# micro.net
KiCad netlist of a schematic drawn in Altium Designer
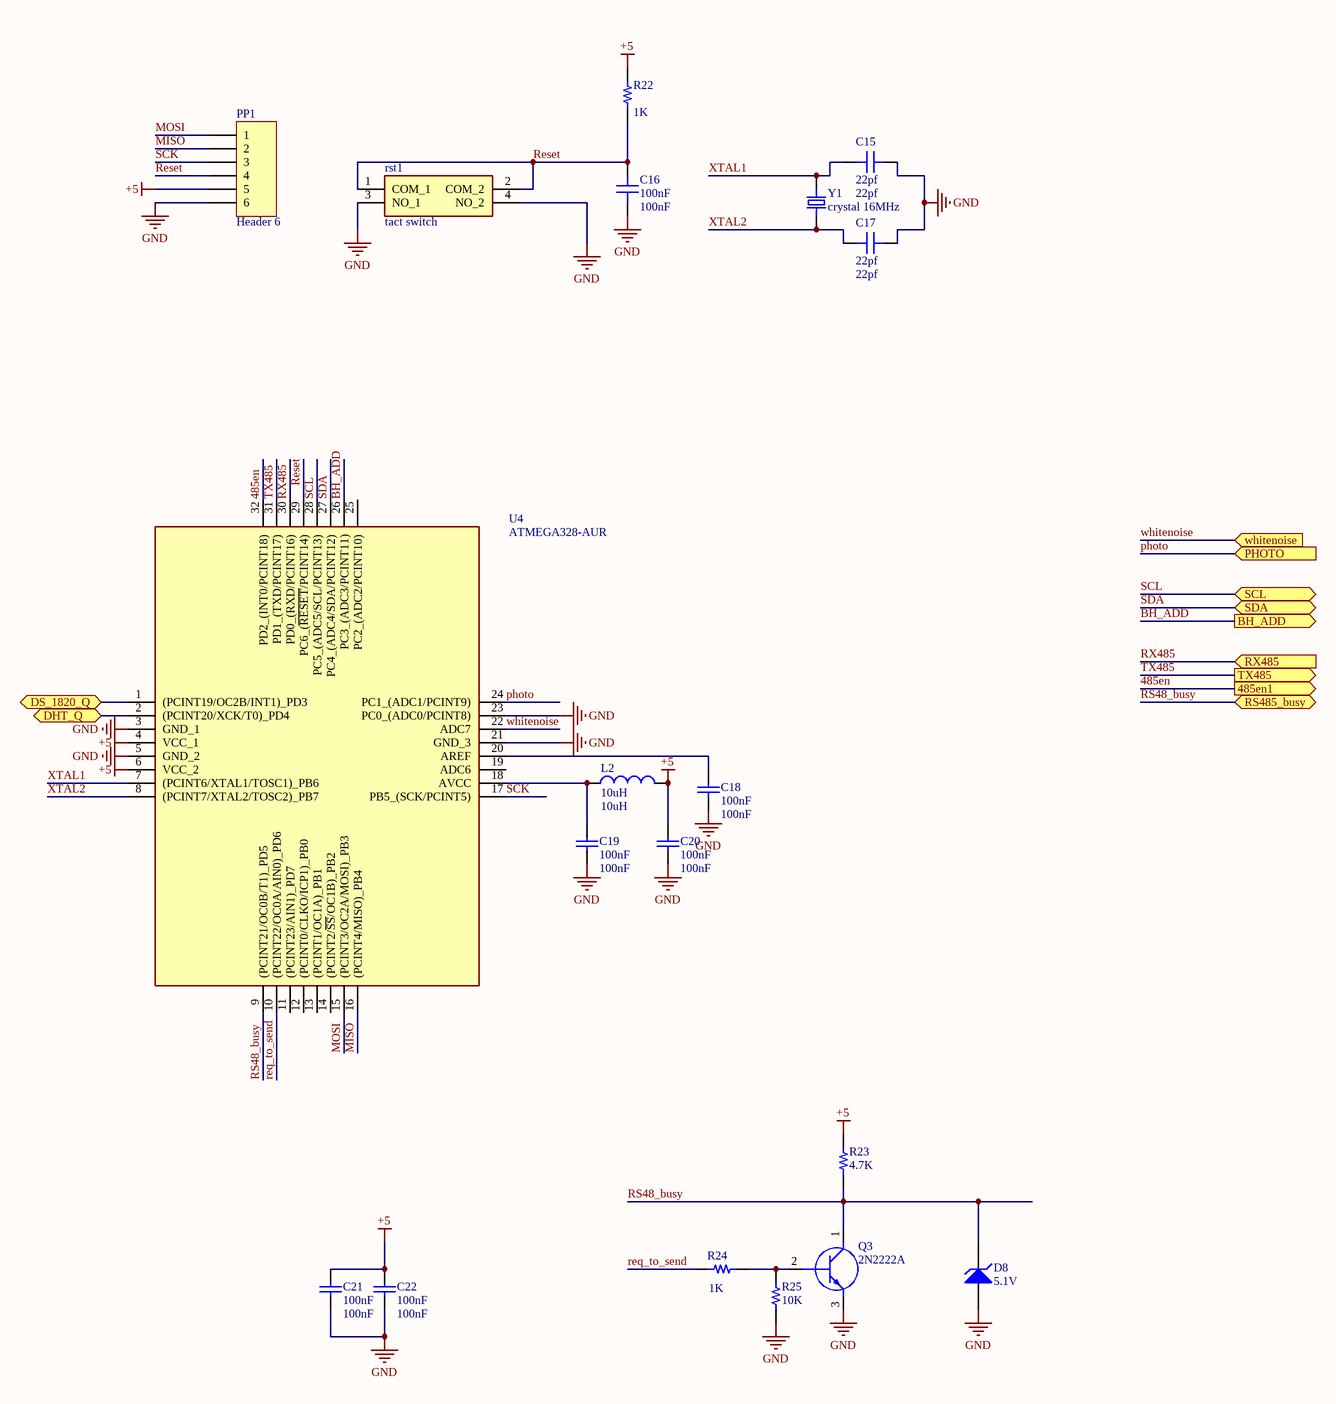
[diagram p0: micro.SchDoc]

(export (version "E")
  (design (tool "Eeschema 10.0.6"))
  (components
    (comp (ref "C15")
      (value "22pf")
      (footprint "0603C")
      (description "CAP SMD 0603")
      (fields (field (name "PART NUMBER") "C0805X106K9RAC7800") (field (name "ALTIUM_VALUE") "22pf"))
      (libsource (lib "lamp control-ver2") (part "Capacitor"))
    )
    (comp (ref "C16")
      (value "100nF")
      (footprint "0603C")
      (description "CAP SMD 0603")
      (fields (field (name "PART NUMBER") "C0805X106K9RAC7800") (field (name "ALTIUM_VALUE") "100nF"))
      (libsource (lib "lamp control-ver2") (part "Capacitor"))
    )
    (comp (ref "C17")
      (value "22pf")
      (footprint "0603C")
      (description "CAP SMD 0603")
      (fields (field (name "PART NUMBER") "C0805X106K9RAC7800") (field (name "ALTIUM_VALUE") "22pf"))
      (libsource (lib "lamp control-ver2") (part "Capacitor"))
    )
    (comp (ref "C18")
      (value "100nF")
      (footprint "0603C")
      (description "CAP SMD 0603")
      (fields (field (name "ALTIUM_VALUE") "100nF") (field (name "PUBLISHER") "Altium Limited"))
      (libsource (lib "Miscellaneous Devices") (part "Cap"))
    )
    (comp (ref "C19")
      (value "100nF")
      (footprint "0603C")
      (description "CAP SMD 0603")
      (fields (field (name "ALTIUM_VALUE") "100nF") (field (name "PUBLISHER") "Altium Limited"))
      (libsource (lib "Miscellaneous Devices") (part "Cap"))
    )
    (comp (ref "C20")
      (value "100nF")
      (footprint "0603C")
      (description "CAP SMD 0603")
      (fields (field (name "ALTIUM_VALUE") "100nF") (field (name "PUBLISHER") "Altium Limited"))
      (libsource (lib "Miscellaneous Devices") (part "Cap"))
    )
    (comp (ref "C21")
      (value "100nF")
      (footprint "0603C")
      (description "CAP SMD 0603")
      (fields (field (name "ALTIUM_VALUE") "100nF") (field (name "PUBLISHER") "Altium Limited"))
      (libsource (lib "Miscellaneous Devices") (part "Cap"))
    )
    (comp (ref "C22")
      (value "100nF")
      (footprint "0603C")
      (description "CAP SMD 0603")
      (fields (field (name "ALTIUM_VALUE") "100nF") (field (name "PUBLISHER") "Altium Limited"))
      (libsource (lib "Miscellaneous Devices") (part "Cap"))
    )
    (comp (ref "D8")
      (value "5.1V")
      (footprint "Diode 1n4148 SMD")
      (description "Zener Diode 5.1v")
      (fields (field (name "PUBLISHER") "Altium Limited"))
      (libsource (lib "Miscellaneous Devices") (part "D Zener"))
    )
    (comp (ref "L2")
      (value "10uH")
      (footprint "IND1206")
      (description "Inductor 1206")
      (fields (field (name "ALTIUM_VALUE") "10uH") (field (name "PUBLISHER") "Altium Limited"))
      (libsource (lib "Miscellaneous Devices") (part "Inductor"))
    )
    (comp (ref "PP1")
      (value "Header 6")
      (footprint "HDR1X6")
      (description "Header, 6-Pin , female")
      (fields (field (name "PUBLISHER") "Altium Limited"))
      (libsource (lib "Miscellaneous Connectors") (part "Header 6"))
    )
    (comp (ref "Q3")
      (value "2N2222A")
      (footprint "soT95p280x130-3n")
      (description "Transistor BJT NPN SMD")
      (libsource (lib "*") (part "2N2222A"))
    )
    (comp (ref "R22")
      (value "1K")
      (footprint "0603R")
      (description "RES SMD 0603")
      (fields (field (name "PART NUMBER") "RCS0805100KFKEA"))
      (libsource (lib "lamp control-ver2") (part "Resistor"))
    )
    (comp (ref "R23")
      (value "4.7K")
      (footprint "0603R")
      (description "RES SMD 0603")
      (fields (field (name "PART NUMBER") "RCS0805100KFKEA"))
      (libsource (lib "lamp control-ver2") (part "Resistor"))
    )
    (comp (ref "R24")
      (value "1K")
      (footprint "0603R")
      (description "RES SMD 0603")
      (fields (field (name "PART NUMBER") "RCS0805100KFKEA"))
      (libsource (lib "lamp control-ver2") (part "Resistor"))
    )
    (comp (ref "R25")
      (value "10K")
      (footprint "0603R")
      (description "RES SMD 0603")
      (fields (field (name "PART NUMBER") "RCS0805100KFKEA"))
      (libsource (lib "lamp control-ver2") (part "Resistor"))
    )
    (comp (ref "rst1")
      (value "tact switch")
      (footprint "DTSM63NVB")
      (description "Push Button SMD - 4PIN")
      (fields
        (field (name "MANUFACTURER_PART_NUMBER") "DTSM-66R-V-T/R")
        (field (name "MOUSER PART NUMBER") "113-DTSM66RVTR")
      )
      (libsource (lib "*") (part "DTSM-66R-V-T_R"))
    )
    (comp (ref "U4")
      (value "ATMEGA328-AUR")
      (footprint "TQFP32_N")
      (description "ATMEGA328p-SMD-LQFP32")
      (fields (field (name "MOUSER PART NUMBER") "556-ATMEGA328-AUR"))
      (libsource (lib "*") (part "ATMEGA328-AUR"))
    )
    (comp (ref "Y1")
      (value "crystal 16MHz")
      (footprint "XTAL_ECS-180-S-5P-DN-TR")
      (description "Crystals 16MHz")
      (fields (field (name "MP") "ECS-180-S-5P-DN-TR") (field (name "MF") "ECS International"))
      (libsource (lib "CrystalSMD") (part "ECS-180-S-5P-DN-TR"))
    )
  )
  (nets
    (net (code "1") (name "+5") (class "Default")
      (node (ref "C20") (pin "1") (pinfunction "1_1") (pintype "passive"))
      (node (ref "C21") (pin "1") (pinfunction "1_1") (pintype "passive"))
      (node (ref "C22") (pin "1") (pinfunction "1_1") (pintype "passive"))
      (node (ref "L2") (pin "2") (pinfunction "2_2") (pintype "passive"))
      (node (ref "PP1") (pin "5") (pinfunction "5_5") (pintype "passive"))
      (node (ref "R22") (pin "2") (pinfunction "2_2") (pintype "passive"))
      (node (ref "R23") (pin "1") (pinfunction "1_1") (pintype "passive"))
      (node (ref "U4") (pin "4") (pinfunction "VCC_1_4") (pintype "passive"))
      (node (ref "U4") (pin "6") (pinfunction "VCC_2_6") (pintype "passive"))
    )
    (net (code "2") (name "/485en") (class "Default")
      (node (ref "U4") (pin "32") (pinfunction "PD2_(INT0/PCINT18)_32") (pintype "passive"))
    )
    (net (code "3") (name "/BH_ADD") (class "Default")
      (node (ref "U4") (pin "26") (pinfunction "PC3_(ADC3/PCINT11)_26") (pintype "passive"))
    )
    (net (code "4") (name "/DHT_Q") (class "Default")
      (node (ref "U4") (pin "2") (pinfunction "(PCINT20/XCK/T0)_PD4_2") (pintype "passive"))
    )
    (net (code "5") (name "/DS_1820_Q") (class "Default")
      (node (ref "U4") (pin "1") (pinfunction "(PCINT19/OC2B/INT1)_PD3_1") (pintype "passive"))
    )
    (net (code "6") (name "/MISO") (class "Default")
      (node (ref "PP1") (pin "2") (pinfunction "2_2") (pintype "passive"))
      (node (ref "U4") (pin "16") (pinfunction "(PCINT4/MISO)_PB4_16") (pintype "passive"))
    )
    (net (code "7") (name "/MOSI") (class "Default")
      (node (ref "PP1") (pin "1") (pinfunction "1_1") (pintype "passive"))
      (node (ref "U4") (pin "15") (pinfunction "(PCINT3/OC2A/MOSI)_PB3_15") (pintype "passive"))
    )
    (net (code "8") (name "/RS48_busy") (class "Default")
      (node (ref "D8") (pin "2") (pinfunction "K_2") (pintype "passive"))
      (node (ref "Q3") (pin "1") (pinfunction "C_1") (pintype "passive"))
      (node (ref "R23") (pin "2") (pinfunction "2_2") (pintype "passive"))
      (node (ref "U4") (pin "9") (pinfunction "(PCINT21/OC0B/T1)_PD5_9") (pintype "passive"))
    )
    (net (code "9") (name "/RX485") (class "Default")
      (node (ref "U4") (pin "30") (pinfunction "PD0_(RXD/PCINT16)_30") (pintype "passive"))
    )
    (net (code "10") (name "/Reset") (class "Default")
      (node (ref "C16") (pin "1") (pinfunction "1_1") (pintype "passive"))
      (node (ref "PP1") (pin "4") (pinfunction "4_4") (pintype "passive"))
      (node (ref "R22") (pin "1") (pinfunction "1_1") (pintype "passive"))
      (node (ref "U4") (pin "29") (pinfunction "PC6_(~{RESET}/PCINT14)_29") (pintype "passive"))
      (node (ref "rst1") (pin "1") (pinfunction "COM_1_1") (pintype "passive"))
      (node (ref "rst1") (pin "2") (pinfunction "COM_2_2") (pintype "passive"))
    )
    (net (code "11") (name "/SCK") (class "Default")
      (node (ref "PP1") (pin "3") (pinfunction "3_3") (pintype "passive"))
      (node (ref "U4") (pin "17") (pinfunction "PB5_(SCK/PCINT5)_17") (pintype "passive"))
    )
    (net (code "12") (name "/SCL") (class "Default")
      (node (ref "U4") (pin "28") (pinfunction "PC5_(ADC5/SCL/PCINT13)_28") (pintype "passive"))
    )
    (net (code "13") (name "/SDA") (class "Default")
      (node (ref "U4") (pin "27") (pinfunction "PC4_(ADC4/SDA/PCINT12)_27") (pintype "passive"))
    )
    (net (code "14") (name "/TX485") (class "Default")
      (node (ref "U4") (pin "31") (pinfunction "PD1_(TXD/PCINT17)_31") (pintype "passive"))
    )
    (net (code "15") (name "/XTAL1") (class "Default")
      (node (ref "C15") (pin "2") (pinfunction "2_2") (pintype "passive"))
      (node (ref "U4") (pin "7") (pinfunction "(PCINT6/XTAL1/TOSC1)_PB6_7") (pintype "passive"))
      (node (ref "Y1") (pin "2") (pinfunction "2_2") (pintype "passive"))
    )
    (net (code "16") (name "/XTAL2") (class "Default")
      (node (ref "C17") (pin "2") (pinfunction "2_2") (pintype "passive"))
      (node (ref "U4") (pin "8") (pinfunction "(PCINT7/XTAL2/TOSC2)_PB7_8") (pintype "passive"))
      (node (ref "Y1") (pin "1") (pinfunction "1_1") (pintype "passive"))
    )
    (net (code "17") (name "/photo") (class "Default")
      (node (ref "U4") (pin "24") (pinfunction "PC1_(ADC1/PCINT9)_24") (pintype "passive"))
    )
    (net (code "18") (name "/req_to_send") (class "Default")
      (node (ref "R24") (pin "2") (pinfunction "2_2") (pintype "passive"))
      (node (ref "U4") (pin "10") (pinfunction "(PCINT22/OC0A/AIN0)_PD6_10") (pintype "passive"))
    )
    (net (code "19") (name "/whitenoise") (class "Default")
      (node (ref "U4") (pin "22") (pinfunction "ADC7_22") (pintype "passive"))
    )
    (net (code "20") (name "GND") (class "Default")
      (node (ref "C15") (pin "1") (pinfunction "1_1") (pintype "passive"))
      (node (ref "C16") (pin "2") (pinfunction "2_2") (pintype "passive"))
      (node (ref "C17") (pin "1") (pinfunction "1_1") (pintype "passive"))
      (node (ref "C18") (pin "2") (pinfunction "2_2") (pintype "passive"))
      (node (ref "C19") (pin "2") (pinfunction "2_2") (pintype "passive"))
      (node (ref "C20") (pin "2") (pinfunction "2_2") (pintype "passive"))
      (node (ref "C21") (pin "2") (pinfunction "2_2") (pintype "passive"))
      (node (ref "C22") (pin "2") (pinfunction "2_2") (pintype "passive"))
      (node (ref "D8") (pin "1") (pinfunction "A_1") (pintype "passive"))
      (node (ref "PP1") (pin "6") (pinfunction "6_6") (pintype "passive"))
      (node (ref "Q3") (pin "3") (pinfunction "E_3") (pintype "passive"))
      (node (ref "R25") (pin "2") (pinfunction "2_2") (pintype "passive"))
      (node (ref "U4") (pin "21") (pinfunction "GND_3_21") (pintype "passive"))
      (node (ref "U4") (pin "23") (pinfunction "PC0_(ADC0/PCINT8)_23") (pintype "passive"))
      (node (ref "U4") (pin "3") (pinfunction "GND_1_3") (pintype "passive"))
      (node (ref "U4") (pin "5") (pinfunction "GND_2_5") (pintype "passive"))
      (node (ref "rst1") (pin "3") (pinfunction "NO_1_3") (pintype "passive"))
      (node (ref "rst1") (pin "4") (pinfunction "NO_2_4") (pintype "passive"))
    )
    (net (code "21") (name "Net-(Q3-B)") (class "Default")
      (node (ref "Q3") (pin "2") (pinfunction "B_2") (pintype "passive"))
      (node (ref "R24") (pin "1") (pinfunction "1_1") (pintype "passive"))
      (node (ref "R25") (pin "1") (pinfunction "1_1") (pintype "passive"))
    )
    (net (code "22") (name "Net-(U4-AREF)") (class "Default")
      (node (ref "C18") (pin "1") (pinfunction "1_1") (pintype "passive"))
      (node (ref "U4") (pin "20") (pinfunction "AREF_20") (pintype "passive"))
    )
    (net (code "23") (name "Net-(U4-AVCC)") (class "Default")
      (node (ref "C19") (pin "1") (pinfunction "1_1") (pintype "passive"))
      (node (ref "L2") (pin "1") (pinfunction "1_1") (pintype "passive"))
      (node (ref "U4") (pin "18") (pinfunction "AVCC_18") (pintype "passive"))
    )
    (net (code "24") (name "unconnected-(U4-(PCINT0{slash}CLKO{slash}ICP1)_PB0-Pad12)") (class "Default")
      (node (ref "U4") (pin "12") (pinfunction "(PCINT0/CLKO/ICP1)_PB0_12") (pintype "passive"))
    )
    (net (code "25") (name "unconnected-(U4-(PCINT1{slash}OC1A)_PB1-Pad13)") (class "Default")
      (node (ref "U4") (pin "13") (pinfunction "(PCINT1/OC1A)_PB1_13") (pintype "passive"))
    )
    (net (code "26") (name "unconnected-(U4-(PCINT2{slash}~{SS}{slash}OC1B)_PB2-Pad14)") (class "Default")
      (node (ref "U4") (pin "14") (pinfunction "(PCINT2/~{SS}/OC1B)_PB2_14") (pintype "passive"))
    )
    (net (code "27") (name "unconnected-(U4-(PCINT23{slash}AIN1)_PD7-Pad11)") (class "Default")
      (node (ref "U4") (pin "11") (pinfunction "(PCINT23/AIN1)_PD7_11") (pintype "passive"))
    )
    (net (code "28") (name "unconnected-(U4-ADC6-Pad19)") (class "Default")
      (node (ref "U4") (pin "19") (pinfunction "ADC6_19") (pintype "passive"))
    )
    (net (code "29") (name "unconnected-(U4-PC2_(ADC2{slash}PCINT10)-Pad25)") (class "Default")
      (node (ref "U4") (pin "25") (pinfunction "PC2_(ADC2/PCINT10)_25") (pintype "passive"))
    )
  )
)
